# LED_DRIVER.net
KiCad netlist of a schematic drawn in EAGLE
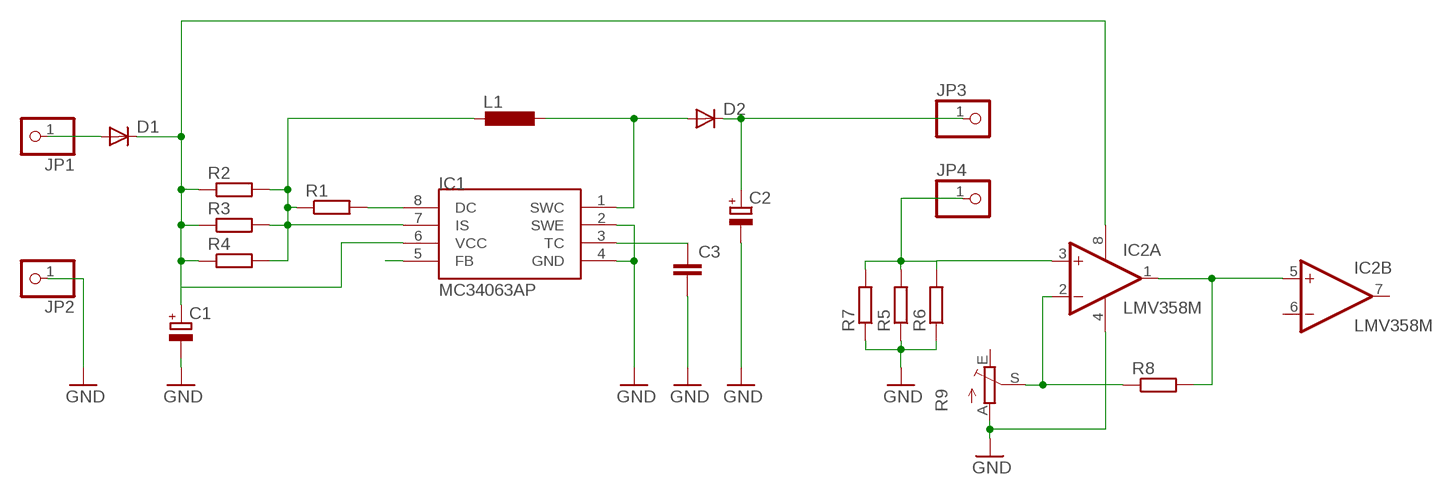
[diagram p0: schematic, sheet 1]

(export (version "E")
  (design (tool "Eeschema 10.0.6"))
  (components
    (comp (ref "C1")
      (value "CPOL-EUE3.5-10")
      (footprint "eagle-import:E3,5-10")
      (libsource (lib "eagle-import") (part "CPOL-EUE3.5-10"))
    )
    (comp (ref "C2")
      (value "CPOL-EUE3.5-10")
      (footprint "eagle-import:E3,5-10")
      (libsource (lib "eagle-import") (part "CPOL-EUE3.5-10"))
    )
    (comp (ref "C3")
      (value "C-EU025-025X050")
      (footprint "eagle-import:C025-025X050")
      (libsource (lib "eagle-import") (part "C-EU025-025X050"))
    )
    (comp (ref "D1")
      (value "DIODE-DO214BA")
      (footprint "eagle-import:DO214BA")
      (libsource (lib "eagle-import") (part "DIODE-DO214BA"))
    )
    (comp (ref "D2")
      (value "DIODE-DO214BA")
      (footprint "eagle-import:DO214BA")
      (libsource (lib "eagle-import") (part "DIODE-DO214BA"))
    )
    (comp (ref "IC1")
      (value "MC34063AP")
      (footprint "eagle-import:DIL08")
      (libsource (lib "eagle-import") (part "MC34063AP"))
    )
    (comp (ref "IC2")
      (value "LMV358M")
      (footprint "eagle-import:SO08")
      (libsource (lib "eagle-import") (part "LMV358?M"))
    )
    (comp (ref "JP1")
      (value "PINHD-1X1")
      (footprint "eagle-import:1X01")
      (libsource (lib "eagle-import") (part "PINHD-1X1"))
    )
    (comp (ref "JP2")
      (value "PINHD-1X1")
      (footprint "eagle-import:1X01")
      (libsource (lib "eagle-import") (part "PINHD-1X1"))
    )
    (comp (ref "JP3")
      (value "PINHD-1X1")
      (footprint "eagle-import:1X01")
      (libsource (lib "eagle-import") (part "PINHD-1X1"))
    )
    (comp (ref "JP4")
      (value "PINHD-1X1")
      (footprint "eagle-import:1X01")
      (libsource (lib "eagle-import") (part "PINHD-1X1"))
    )
    (comp (ref "L1")
      (value "DO3316P")
      (footprint "eagle-import:DO3316P")
      (libsource (lib "eagle-import") (part "DO3316P"))
    )
    (comp (ref "R1")
      (value "R-EU_R1206W")
      (footprint "eagle-import:R1206W")
      (libsource (lib "eagle-import") (part "R-EU_R1206W"))
    )
    (comp (ref "R2")
      (value "R-EU_R1206W")
      (footprint "eagle-import:R1206W")
      (libsource (lib "eagle-import") (part "R-EU_R1206W"))
    )
    (comp (ref "R3")
      (value "R-EU_R1206W")
      (footprint "eagle-import:R1206W")
      (libsource (lib "eagle-import") (part "R-EU_R1206W"))
    )
    (comp (ref "R4")
      (value "R-EU_R1206W")
      (footprint "eagle-import:R1206W")
      (libsource (lib "eagle-import") (part "R-EU_R1206W"))
    )
    (comp (ref "R5")
      (value "R-EU_R1206W")
      (footprint "eagle-import:R1206W")
      (libsource (lib "eagle-import") (part "R-EU_R1206W"))
    )
    (comp (ref "R6")
      (value "R-EU_R1206W")
      (footprint "eagle-import:R1206W")
      (libsource (lib "eagle-import") (part "R-EU_R1206W"))
    )
    (comp (ref "R7")
      (value "R-EU_R1206W")
      (footprint "eagle-import:R1206W")
      (libsource (lib "eagle-import") (part "R-EU_R1206W"))
    )
    (comp (ref "R8")
      (value "R-EU_R1206W")
      (footprint "eagle-import:R1206W")
      (libsource (lib "eagle-import") (part "R-EU_R1206W"))
    )
    (comp (ref "R9")
      (value "TRIM_EU-S64W")
      (footprint "eagle-import:S64W")
      (libsource (lib "eagle-import") (part "TRIM_EU-S64W"))
    )
  )
  (nets
    (net (code "1") (name "GND") (class "Default")
      (node (ref "C1") (pin "-") (pinfunction "-_-") (pintype "passive"))
      (node (ref "C2") (pin "-") (pinfunction "-_-") (pintype "passive"))
      (node (ref "C3") (pin "2") (pinfunction "2_2") (pintype "passive"))
      (node (ref "IC1") (pin "2") (pinfunction "SWE_2") (pintype "passive"))
      (node (ref "IC1") (pin "4") (pinfunction "GND_4") (pintype "passive"))
      (node (ref "IC2") (pin "4") (pinfunction "V-_4") (pintype "power_in"))
      (node (ref "JP2") (pin "1") (pinfunction "1_1") (pintype "passive"))
      (node (ref "R5") (pin "1") (pinfunction "1_1") (pintype "passive"))
      (node (ref "R6") (pin "1") (pinfunction "1_1") (pintype "passive"))
      (node (ref "R7") (pin "1") (pinfunction "1_1") (pintype "passive"))
      (node (ref "R9") (pin "A") (pinfunction "A_A") (pintype "passive"))
    )
    (net (code "2") (name "Net-(C2-Pad+)") (class "Default")
      (node (ref "C2") (pin "+") (pinfunction "+_+") (pintype "passive"))
      (node (ref "D2") (pin "C") (pinfunction "C_C") (pintype "passive"))
      (node (ref "JP3") (pin "1") (pinfunction "1_1") (pintype "passive"))
    )
    (net (code "3") (name "Net-(D1-PadA)") (class "Default")
      (node (ref "D1") (pin "A") (pinfunction "A_A") (pintype "passive"))
      (node (ref "JP1") (pin "1") (pinfunction "1_1") (pintype "passive"))
    )
    (net (code "4") (name "Net-(IC1-DC)") (class "Default")
      (node (ref "IC1") (pin "8") (pinfunction "DC_8") (pintype "passive"))
      (node (ref "R1") (pin "2") (pinfunction "2_2") (pintype "passive"))
    )
    (net (code "5") (name "Net-(IC1-IS)") (class "Default")
      (node (ref "IC1") (pin "7") (pinfunction "IS_7") (pintype "passive"))
      (node (ref "L1") (pin "1") (pinfunction "1_1") (pintype "passive"))
      (node (ref "R1") (pin "1") (pinfunction "1_1") (pintype "passive"))
      (node (ref "R2") (pin "2") (pinfunction "2_2") (pintype "passive"))
      (node (ref "R3") (pin "2") (pinfunction "2_2") (pintype "passive"))
      (node (ref "R4") (pin "2") (pinfunction "2_2") (pintype "passive"))
    )
    (net (code "6") (name "Net-(IC1-SWC)") (class "Default")
      (node (ref "D2") (pin "A") (pinfunction "A_A") (pintype "passive"))
      (node (ref "IC1") (pin "1") (pinfunction "SWC_1") (pintype "passive"))
      (node (ref "L1") (pin "2") (pinfunction "2_2") (pintype "passive"))
    )
    (net (code "7") (name "Net-(IC1-TC)") (class "Default")
      (node (ref "C3") (pin "1") (pinfunction "1_1") (pintype "passive"))
      (node (ref "IC1") (pin "3") (pinfunction "TC_3") (pintype "passive"))
    )
    (net (code "8") (name "Net-(IC1-VCC)") (class "Default")
      (node (ref "C1") (pin "+") (pinfunction "+_+") (pintype "passive"))
      (node (ref "D1") (pin "C") (pinfunction "C_C") (pintype "passive"))
      (node (ref "IC1") (pin "6") (pinfunction "VCC_6") (pintype "passive"))
      (node (ref "IC2") (pin "8") (pinfunction "V+_8") (pintype "power_in"))
      (node (ref "R2") (pin "1") (pinfunction "1_1") (pintype "passive"))
      (node (ref "R3") (pin "1") (pinfunction "1_1") (pintype "passive"))
      (node (ref "R4") (pin "1") (pinfunction "1_1") (pintype "passive"))
    )
    (net (code "9") (name "Net-(IC2A-+IN)") (class "Default")
      (node (ref "IC2") (pin "3") (pinfunction "+IN_3") (pintype "input"))
      (node (ref "JP4") (pin "1") (pinfunction "1_1") (pintype "passive"))
      (node (ref "R5") (pin "2") (pinfunction "2_2") (pintype "passive"))
      (node (ref "R6") (pin "2") (pinfunction "2_2") (pintype "passive"))
      (node (ref "R7") (pin "2") (pinfunction "2_2") (pintype "passive"))
    )
    (net (code "10") (name "Net-(IC2A--IN)") (class "Default")
      (node (ref "IC2") (pin "2") (pinfunction "-IN_2") (pintype "input"))
      (node (ref "R8") (pin "1") (pinfunction "1_1") (pintype "passive"))
      (node (ref "R9") (pin "S") (pinfunction "S_S") (pintype "passive"))
    )
    (net (code "11") (name "Net-(IC2A-OUT)") (class "Default")
      (node (ref "IC2") (pin "1") (pinfunction "OUT_1") (pintype "output"))
      (node (ref "IC2") (pin "5") (pinfunction "+IN_5") (pintype "input"))
      (node (ref "R8") (pin "2") (pinfunction "2_2") (pintype "passive"))
    )
    (net (code "12") (name "unconnected-(IC1-FB-Pad5)") (class "Default")
      (node (ref "IC1") (pin "5") (pinfunction "FB_5") (pintype "passive"))
    )
    (net (code "13") (name "unconnected-(IC2B--IN-Pad6)") (class "Default")
      (node (ref "IC2") (pin "6") (pinfunction "-IN_6") (pintype "input"))
    )
    (net (code "14") (name "unconnected-(IC2B-OUT-Pad7)") (class "Default")
      (node (ref "IC2") (pin "7") (pinfunction "OUT_7") (pintype "output"))
    )
    (net (code "15") (name "unconnected-(R9-PadE)") (class "Default")
      (node (ref "R9") (pin "E") (pinfunction "E_E") (pintype "passive"))
    )
  )
)
